# 8_R_G_B_LEDs.net
KiCad netlist of a schematic drawn in EAGLE
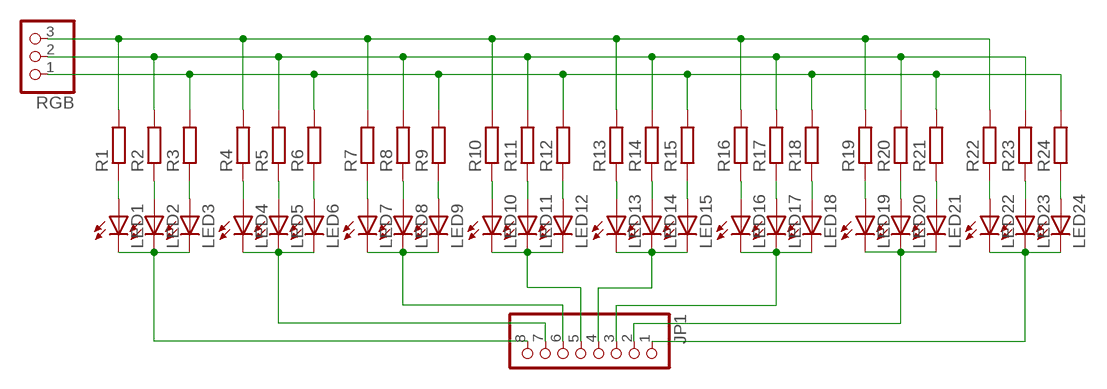
[diagram p0: schematic, sheet 1]

(export (version "E")
  (design (tool "Eeschema 10.0.6"))
  (components
    (comp (ref "JP1")
      (value "PINHD-1X8")
      (footprint "eagle-import:1X08")
      (libsource (lib "eagle-import") (part "PINHD-1X8"))
    )
    (comp (ref "LED1")
      (value "LED5MM")
      (footprint "eagle-import:LED5MM")
      (libsource (lib "eagle-import") (part "LED5MM"))
    )
    (comp (ref "LED2")
      (value "LED5MM")
      (footprint "eagle-import:LED5MM")
      (libsource (lib "eagle-import") (part "LED5MM"))
    )
    (comp (ref "LED3")
      (value "LED5MM")
      (footprint "eagle-import:LED5MM")
      (libsource (lib "eagle-import") (part "LED5MM"))
    )
    (comp (ref "LED4")
      (value "LED5MM")
      (footprint "eagle-import:LED5MM")
      (libsource (lib "eagle-import") (part "LED5MM"))
    )
    (comp (ref "LED5")
      (value "LED5MM")
      (footprint "eagle-import:LED5MM")
      (libsource (lib "eagle-import") (part "LED5MM"))
    )
    (comp (ref "LED6")
      (value "LED5MM")
      (footprint "eagle-import:LED5MM")
      (libsource (lib "eagle-import") (part "LED5MM"))
    )
    (comp (ref "LED7")
      (value "LED5MM")
      (footprint "eagle-import:LED5MM")
      (libsource (lib "eagle-import") (part "LED5MM"))
    )
    (comp (ref "LED8")
      (value "LED5MM")
      (footprint "eagle-import:LED5MM")
      (libsource (lib "eagle-import") (part "LED5MM"))
    )
    (comp (ref "LED9")
      (value "LED5MM")
      (footprint "eagle-import:LED5MM")
      (libsource (lib "eagle-import") (part "LED5MM"))
    )
    (comp (ref "LED10")
      (value "LED5MM")
      (footprint "eagle-import:LED5MM")
      (libsource (lib "eagle-import") (part "LED5MM"))
    )
    (comp (ref "LED11")
      (value "LED5MM")
      (footprint "eagle-import:LED5MM")
      (libsource (lib "eagle-import") (part "LED5MM"))
    )
    (comp (ref "LED12")
      (value "LED5MM")
      (footprint "eagle-import:LED5MM")
      (libsource (lib "eagle-import") (part "LED5MM"))
    )
    (comp (ref "LED13")
      (value "LED5MM")
      (footprint "eagle-import:LED5MM")
      (libsource (lib "eagle-import") (part "LED5MM"))
    )
    (comp (ref "LED14")
      (value "LED5MM")
      (footprint "eagle-import:LED5MM")
      (libsource (lib "eagle-import") (part "LED5MM"))
    )
    (comp (ref "LED15")
      (value "LED5MM")
      (footprint "eagle-import:LED5MM")
      (libsource (lib "eagle-import") (part "LED5MM"))
    )
    (comp (ref "LED16")
      (value "LED5MM")
      (footprint "eagle-import:LED5MM")
      (libsource (lib "eagle-import") (part "LED5MM"))
    )
    (comp (ref "LED17")
      (value "LED5MM")
      (footprint "eagle-import:LED5MM")
      (libsource (lib "eagle-import") (part "LED5MM"))
    )
    (comp (ref "LED18")
      (value "LED5MM")
      (footprint "eagle-import:LED5MM")
      (libsource (lib "eagle-import") (part "LED5MM"))
    )
    (comp (ref "LED19")
      (value "LED5MM")
      (footprint "eagle-import:LED5MM")
      (libsource (lib "eagle-import") (part "LED5MM"))
    )
    (comp (ref "LED20")
      (value "LED5MM")
      (footprint "eagle-import:LED5MM")
      (libsource (lib "eagle-import") (part "LED5MM"))
    )
    (comp (ref "LED21")
      (value "LED5MM")
      (footprint "eagle-import:LED5MM")
      (libsource (lib "eagle-import") (part "LED5MM"))
    )
    (comp (ref "LED22")
      (value "LED5MM")
      (footprint "eagle-import:LED5MM")
      (libsource (lib "eagle-import") (part "LED5MM"))
    )
    (comp (ref "LED23")
      (value "LED5MM")
      (footprint "eagle-import:LED5MM")
      (libsource (lib "eagle-import") (part "LED5MM"))
    )
    (comp (ref "LED24")
      (value "LED5MM")
      (footprint "eagle-import:LED5MM")
      (libsource (lib "eagle-import") (part "LED5MM"))
    )
    (comp (ref "R1")
      (value "R-EU_0207/7")
      (footprint "eagle-import:0207_7")
      (libsource (lib "eagle-import") (part "R-EU_0207/7"))
    )
    (comp (ref "R2")
      (value "R-EU_0207/7")
      (footprint "eagle-import:0207_7")
      (libsource (lib "eagle-import") (part "R-EU_0207/7"))
    )
    (comp (ref "R3")
      (value "R-EU_0207/7")
      (footprint "eagle-import:0207_7")
      (libsource (lib "eagle-import") (part "R-EU_0207/7"))
    )
    (comp (ref "R4")
      (value "R-EU_0207/7")
      (footprint "eagle-import:0207_7")
      (libsource (lib "eagle-import") (part "R-EU_0207/7"))
    )
    (comp (ref "R5")
      (value "R-EU_0207/7")
      (footprint "eagle-import:0207_7")
      (libsource (lib "eagle-import") (part "R-EU_0207/7"))
    )
    (comp (ref "R6")
      (value "R-EU_0207/7")
      (footprint "eagle-import:0207_7")
      (libsource (lib "eagle-import") (part "R-EU_0207/7"))
    )
    (comp (ref "R7")
      (value "R-EU_0207/7")
      (footprint "eagle-import:0207_7")
      (libsource (lib "eagle-import") (part "R-EU_0207/7"))
    )
    (comp (ref "R8")
      (value "R-EU_0207/7")
      (footprint "eagle-import:0207_7")
      (libsource (lib "eagle-import") (part "R-EU_0207/7"))
    )
    (comp (ref "R9")
      (value "R-EU_0207/7")
      (footprint "eagle-import:0207_7")
      (libsource (lib "eagle-import") (part "R-EU_0207/7"))
    )
    (comp (ref "R10")
      (value "R-EU_0207/7")
      (footprint "eagle-import:0207_7")
      (libsource (lib "eagle-import") (part "R-EU_0207/7"))
    )
    (comp (ref "R11")
      (value "R-EU_0207/7")
      (footprint "eagle-import:0207_7")
      (libsource (lib "eagle-import") (part "R-EU_0207/7"))
    )
    (comp (ref "R12")
      (value "R-EU_0207/7")
      (footprint "eagle-import:0207_7")
      (libsource (lib "eagle-import") (part "R-EU_0207/7"))
    )
    (comp (ref "R13")
      (value "R-EU_0207/7")
      (footprint "eagle-import:0207_7")
      (libsource (lib "eagle-import") (part "R-EU_0207/7"))
    )
    (comp (ref "R14")
      (value "R-EU_0207/7")
      (footprint "eagle-import:0207_7")
      (libsource (lib "eagle-import") (part "R-EU_0207/7"))
    )
    (comp (ref "R15")
      (value "R-EU_0207/7")
      (footprint "eagle-import:0207_7")
      (libsource (lib "eagle-import") (part "R-EU_0207/7"))
    )
    (comp (ref "R16")
      (value "R-EU_0207/7")
      (footprint "eagle-import:0207_7")
      (libsource (lib "eagle-import") (part "R-EU_0207/7"))
    )
    (comp (ref "R17")
      (value "R-EU_0207/7")
      (footprint "eagle-import:0207_7")
      (libsource (lib "eagle-import") (part "R-EU_0207/7"))
    )
    (comp (ref "R18")
      (value "R-EU_0207/7")
      (footprint "eagle-import:0207_7")
      (libsource (lib "eagle-import") (part "R-EU_0207/7"))
    )
    (comp (ref "R19")
      (value "R-EU_0207/7")
      (footprint "eagle-import:0207_7")
      (libsource (lib "eagle-import") (part "R-EU_0207/7"))
    )
    (comp (ref "R20")
      (value "R-EU_0207/7")
      (footprint "eagle-import:0207_7")
      (libsource (lib "eagle-import") (part "R-EU_0207/7"))
    )
    (comp (ref "R21")
      (value "R-EU_0207/7")
      (footprint "eagle-import:0207_7")
      (libsource (lib "eagle-import") (part "R-EU_0207/7"))
    )
    (comp (ref "R22")
      (value "R-EU_0207/7")
      (footprint "eagle-import:0207_7")
      (libsource (lib "eagle-import") (part "R-EU_0207/7"))
    )
    (comp (ref "R23")
      (value "R-EU_0207/7")
      (footprint "eagle-import:0207_7")
      (libsource (lib "eagle-import") (part "R-EU_0207/7"))
    )
    (comp (ref "R24")
      (value "R-EU_0207/7")
      (footprint "eagle-import:0207_7")
      (libsource (lib "eagle-import") (part "R-EU_0207/7"))
    )
    (comp (ref "RGB")
      (value "PINHD-1X3")
      (footprint "eagle-import:1X03")
      (libsource (lib "eagle-import") (part "PINHD-1X3"))
    )
  )
  (nets
    (net (code "1") (name "Net-(LED1-C)") (class "Default")
      (node (ref "JP1") (pin "8") (pinfunction "8_8") (pintype "passive"))
      (node (ref "LED1") (pin "K") (pinfunction "C_K") (pintype "passive"))
      (node (ref "LED2") (pin "K") (pinfunction "C_K") (pintype "passive"))
      (node (ref "LED3") (pin "K") (pinfunction "C_K") (pintype "passive"))
    )
    (net (code "2") (name "Net-(LED1-PadA)") (class "Default")
      (node (ref "LED1") (pin "A") (pinfunction "A_A") (pintype "passive"))
      (node (ref "R1") (pin "1") (pinfunction "1_1") (pintype "passive"))
    )
    (net (code "3") (name "Net-(LED2-PadA)") (class "Default")
      (node (ref "LED2") (pin "A") (pinfunction "A_A") (pintype "passive"))
      (node (ref "R2") (pin "1") (pinfunction "1_1") (pintype "passive"))
    )
    (net (code "4") (name "Net-(LED3-PadA)") (class "Default")
      (node (ref "LED3") (pin "A") (pinfunction "A_A") (pintype "passive"))
      (node (ref "R3") (pin "1") (pinfunction "1_1") (pintype "passive"))
    )
    (net (code "5") (name "Net-(LED4-C)") (class "Default")
      (node (ref "JP1") (pin "7") (pinfunction "7_7") (pintype "passive"))
      (node (ref "LED4") (pin "K") (pinfunction "C_K") (pintype "passive"))
      (node (ref "LED5") (pin "K") (pinfunction "C_K") (pintype "passive"))
      (node (ref "LED6") (pin "K") (pinfunction "C_K") (pintype "passive"))
    )
    (net (code "6") (name "Net-(LED4-PadA)") (class "Default")
      (node (ref "LED4") (pin "A") (pinfunction "A_A") (pintype "passive"))
      (node (ref "R4") (pin "1") (pinfunction "1_1") (pintype "passive"))
    )
    (net (code "7") (name "Net-(LED5-PadA)") (class "Default")
      (node (ref "LED5") (pin "A") (pinfunction "A_A") (pintype "passive"))
      (node (ref "R5") (pin "1") (pinfunction "1_1") (pintype "passive"))
    )
    (net (code "8") (name "Net-(LED6-PadA)") (class "Default")
      (node (ref "LED6") (pin "A") (pinfunction "A_A") (pintype "passive"))
      (node (ref "R6") (pin "1") (pinfunction "1_1") (pintype "passive"))
    )
    (net (code "9") (name "Net-(LED7-C)") (class "Default")
      (node (ref "JP1") (pin "6") (pinfunction "6_6") (pintype "passive"))
      (node (ref "LED7") (pin "K") (pinfunction "C_K") (pintype "passive"))
      (node (ref "LED8") (pin "K") (pinfunction "C_K") (pintype "passive"))
      (node (ref "LED9") (pin "K") (pinfunction "C_K") (pintype "passive"))
    )
    (net (code "10") (name "Net-(LED7-PadA)") (class "Default")
      (node (ref "LED7") (pin "A") (pinfunction "A_A") (pintype "passive"))
      (node (ref "R7") (pin "1") (pinfunction "1_1") (pintype "passive"))
    )
    (net (code "11") (name "Net-(LED8-PadA)") (class "Default")
      (node (ref "LED8") (pin "A") (pinfunction "A_A") (pintype "passive"))
      (node (ref "R8") (pin "1") (pinfunction "1_1") (pintype "passive"))
    )
    (net (code "12") (name "Net-(LED9-PadA)") (class "Default")
      (node (ref "LED9") (pin "A") (pinfunction "A_A") (pintype "passive"))
      (node (ref "R9") (pin "1") (pinfunction "1_1") (pintype "passive"))
    )
    (net (code "13") (name "Net-(LED10-C)") (class "Default")
      (node (ref "JP1") (pin "5") (pinfunction "5_5") (pintype "passive"))
      (node (ref "LED10") (pin "K") (pinfunction "C_K") (pintype "passive"))
      (node (ref "LED11") (pin "K") (pinfunction "C_K") (pintype "passive"))
      (node (ref "LED12") (pin "K") (pinfunction "C_K") (pintype "passive"))
    )
    (net (code "14") (name "Net-(LED10-PadA)") (class "Default")
      (node (ref "LED10") (pin "A") (pinfunction "A_A") (pintype "passive"))
      (node (ref "R10") (pin "1") (pinfunction "1_1") (pintype "passive"))
    )
    (net (code "15") (name "Net-(LED11-PadA)") (class "Default")
      (node (ref "LED11") (pin "A") (pinfunction "A_A") (pintype "passive"))
      (node (ref "R11") (pin "1") (pinfunction "1_1") (pintype "passive"))
    )
    (net (code "16") (name "Net-(LED12-PadA)") (class "Default")
      (node (ref "LED12") (pin "A") (pinfunction "A_A") (pintype "passive"))
      (node (ref "R12") (pin "1") (pinfunction "1_1") (pintype "passive"))
    )
    (net (code "17") (name "Net-(LED13-C)") (class "Default")
      (node (ref "JP1") (pin "4") (pinfunction "4_4") (pintype "passive"))
      (node (ref "LED13") (pin "K") (pinfunction "C_K") (pintype "passive"))
      (node (ref "LED14") (pin "K") (pinfunction "C_K") (pintype "passive"))
      (node (ref "LED15") (pin "K") (pinfunction "C_K") (pintype "passive"))
    )
    (net (code "18") (name "Net-(LED13-PadA)") (class "Default")
      (node (ref "LED13") (pin "A") (pinfunction "A_A") (pintype "passive"))
      (node (ref "R13") (pin "1") (pinfunction "1_1") (pintype "passive"))
    )
    (net (code "19") (name "Net-(LED14-PadA)") (class "Default")
      (node (ref "LED14") (pin "A") (pinfunction "A_A") (pintype "passive"))
      (node (ref "R14") (pin "1") (pinfunction "1_1") (pintype "passive"))
    )
    (net (code "20") (name "Net-(LED15-PadA)") (class "Default")
      (node (ref "LED15") (pin "A") (pinfunction "A_A") (pintype "passive"))
      (node (ref "R15") (pin "1") (pinfunction "1_1") (pintype "passive"))
    )
    (net (code "21") (name "Net-(LED16-C)") (class "Default")
      (node (ref "JP1") (pin "3") (pinfunction "3_3") (pintype "passive"))
      (node (ref "LED16") (pin "K") (pinfunction "C_K") (pintype "passive"))
      (node (ref "LED17") (pin "K") (pinfunction "C_K") (pintype "passive"))
      (node (ref "LED18") (pin "K") (pinfunction "C_K") (pintype "passive"))
    )
    (net (code "22") (name "Net-(LED16-PadA)") (class "Default")
      (node (ref "LED16") (pin "A") (pinfunction "A_A") (pintype "passive"))
      (node (ref "R16") (pin "1") (pinfunction "1_1") (pintype "passive"))
    )
    (net (code "23") (name "Net-(LED17-PadA)") (class "Default")
      (node (ref "LED17") (pin "A") (pinfunction "A_A") (pintype "passive"))
      (node (ref "R17") (pin "1") (pinfunction "1_1") (pintype "passive"))
    )
    (net (code "24") (name "Net-(LED18-PadA)") (class "Default")
      (node (ref "LED18") (pin "A") (pinfunction "A_A") (pintype "passive"))
      (node (ref "R18") (pin "1") (pinfunction "1_1") (pintype "passive"))
    )
    (net (code "25") (name "Net-(LED19-C)") (class "Default")
      (node (ref "JP1") (pin "2") (pinfunction "2_2") (pintype "passive"))
      (node (ref "LED19") (pin "K") (pinfunction "C_K") (pintype "passive"))
      (node (ref "LED20") (pin "K") (pinfunction "C_K") (pintype "passive"))
      (node (ref "LED21") (pin "K") (pinfunction "C_K") (pintype "passive"))
    )
    (net (code "26") (name "Net-(LED19-PadA)") (class "Default")
      (node (ref "LED19") (pin "A") (pinfunction "A_A") (pintype "passive"))
      (node (ref "R19") (pin "1") (pinfunction "1_1") (pintype "passive"))
    )
    (net (code "27") (name "Net-(LED20-PadA)") (class "Default")
      (node (ref "LED20") (pin "A") (pinfunction "A_A") (pintype "passive"))
      (node (ref "R20") (pin "1") (pinfunction "1_1") (pintype "passive"))
    )
    (net (code "28") (name "Net-(LED21-PadA)") (class "Default")
      (node (ref "LED21") (pin "A") (pinfunction "A_A") (pintype "passive"))
      (node (ref "R21") (pin "1") (pinfunction "1_1") (pintype "passive"))
    )
    (net (code "29") (name "Net-(LED22-C)") (class "Default")
      (node (ref "JP1") (pin "1") (pinfunction "1_1") (pintype "passive"))
      (node (ref "LED22") (pin "K") (pinfunction "C_K") (pintype "passive"))
      (node (ref "LED23") (pin "K") (pinfunction "C_K") (pintype "passive"))
      (node (ref "LED24") (pin "K") (pinfunction "C_K") (pintype "passive"))
    )
    (net (code "30") (name "Net-(LED22-PadA)") (class "Default")
      (node (ref "LED22") (pin "A") (pinfunction "A_A") (pintype "passive"))
      (node (ref "R22") (pin "1") (pinfunction "1_1") (pintype "passive"))
    )
    (net (code "31") (name "Net-(LED23-PadA)") (class "Default")
      (node (ref "LED23") (pin "A") (pinfunction "A_A") (pintype "passive"))
      (node (ref "R23") (pin "1") (pinfunction "1_1") (pintype "passive"))
    )
    (net (code "32") (name "Net-(LED24-PadA)") (class "Default")
      (node (ref "LED24") (pin "A") (pinfunction "A_A") (pintype "passive"))
      (node (ref "R24") (pin "1") (pinfunction "1_1") (pintype "passive"))
    )
    (net (code "33") (name "Net-(R1-Pad2)") (class "Default")
      (node (ref "R1") (pin "2") (pinfunction "2_2") (pintype "passive"))
      (node (ref "R10") (pin "2") (pinfunction "2_2") (pintype "passive"))
      (node (ref "R13") (pin "2") (pinfunction "2_2") (pintype "passive"))
      (node (ref "R16") (pin "2") (pinfunction "2_2") (pintype "passive"))
      (node (ref "R19") (pin "2") (pinfunction "2_2") (pintype "passive"))
      (node (ref "R22") (pin "2") (pinfunction "2_2") (pintype "passive"))
      (node (ref "R4") (pin "2") (pinfunction "2_2") (pintype "passive"))
      (node (ref "R7") (pin "2") (pinfunction "2_2") (pintype "passive"))
      (node (ref "RGB") (pin "3") (pinfunction "3_3") (pintype "passive"))
    )
    (net (code "34") (name "Net-(R11-Pad2)") (class "Default")
      (node (ref "R11") (pin "2") (pinfunction "2_2") (pintype "passive"))
      (node (ref "R14") (pin "2") (pinfunction "2_2") (pintype "passive"))
      (node (ref "R17") (pin "2") (pinfunction "2_2") (pintype "passive"))
      (node (ref "R2") (pin "2") (pinfunction "2_2") (pintype "passive"))
      (node (ref "R20") (pin "2") (pinfunction "2_2") (pintype "passive"))
      (node (ref "R23") (pin "2") (pinfunction "2_2") (pintype "passive"))
      (node (ref "R5") (pin "2") (pinfunction "2_2") (pintype "passive"))
      (node (ref "R8") (pin "2") (pinfunction "2_2") (pintype "passive"))
      (node (ref "RGB") (pin "2") (pinfunction "2_2") (pintype "passive"))
    )
    (net (code "35") (name "Net-(R12-Pad2)") (class "Default")
      (node (ref "R12") (pin "2") (pinfunction "2_2") (pintype "passive"))
      (node (ref "R15") (pin "2") (pinfunction "2_2") (pintype "passive"))
      (node (ref "R18") (pin "2") (pinfunction "2_2") (pintype "passive"))
      (node (ref "R21") (pin "2") (pinfunction "2_2") (pintype "passive"))
      (node (ref "R24") (pin "2") (pinfunction "2_2") (pintype "passive"))
      (node (ref "R3") (pin "2") (pinfunction "2_2") (pintype "passive"))
      (node (ref "R6") (pin "2") (pinfunction "2_2") (pintype "passive"))
      (node (ref "R9") (pin "2") (pinfunction "2_2") (pintype "passive"))
      (node (ref "RGB") (pin "1") (pinfunction "1_1") (pintype "passive"))
    )
  )
)
